# quad-hybrid-QCN-19D.net
KiCad netlist of a schematic drawn in EAGLE
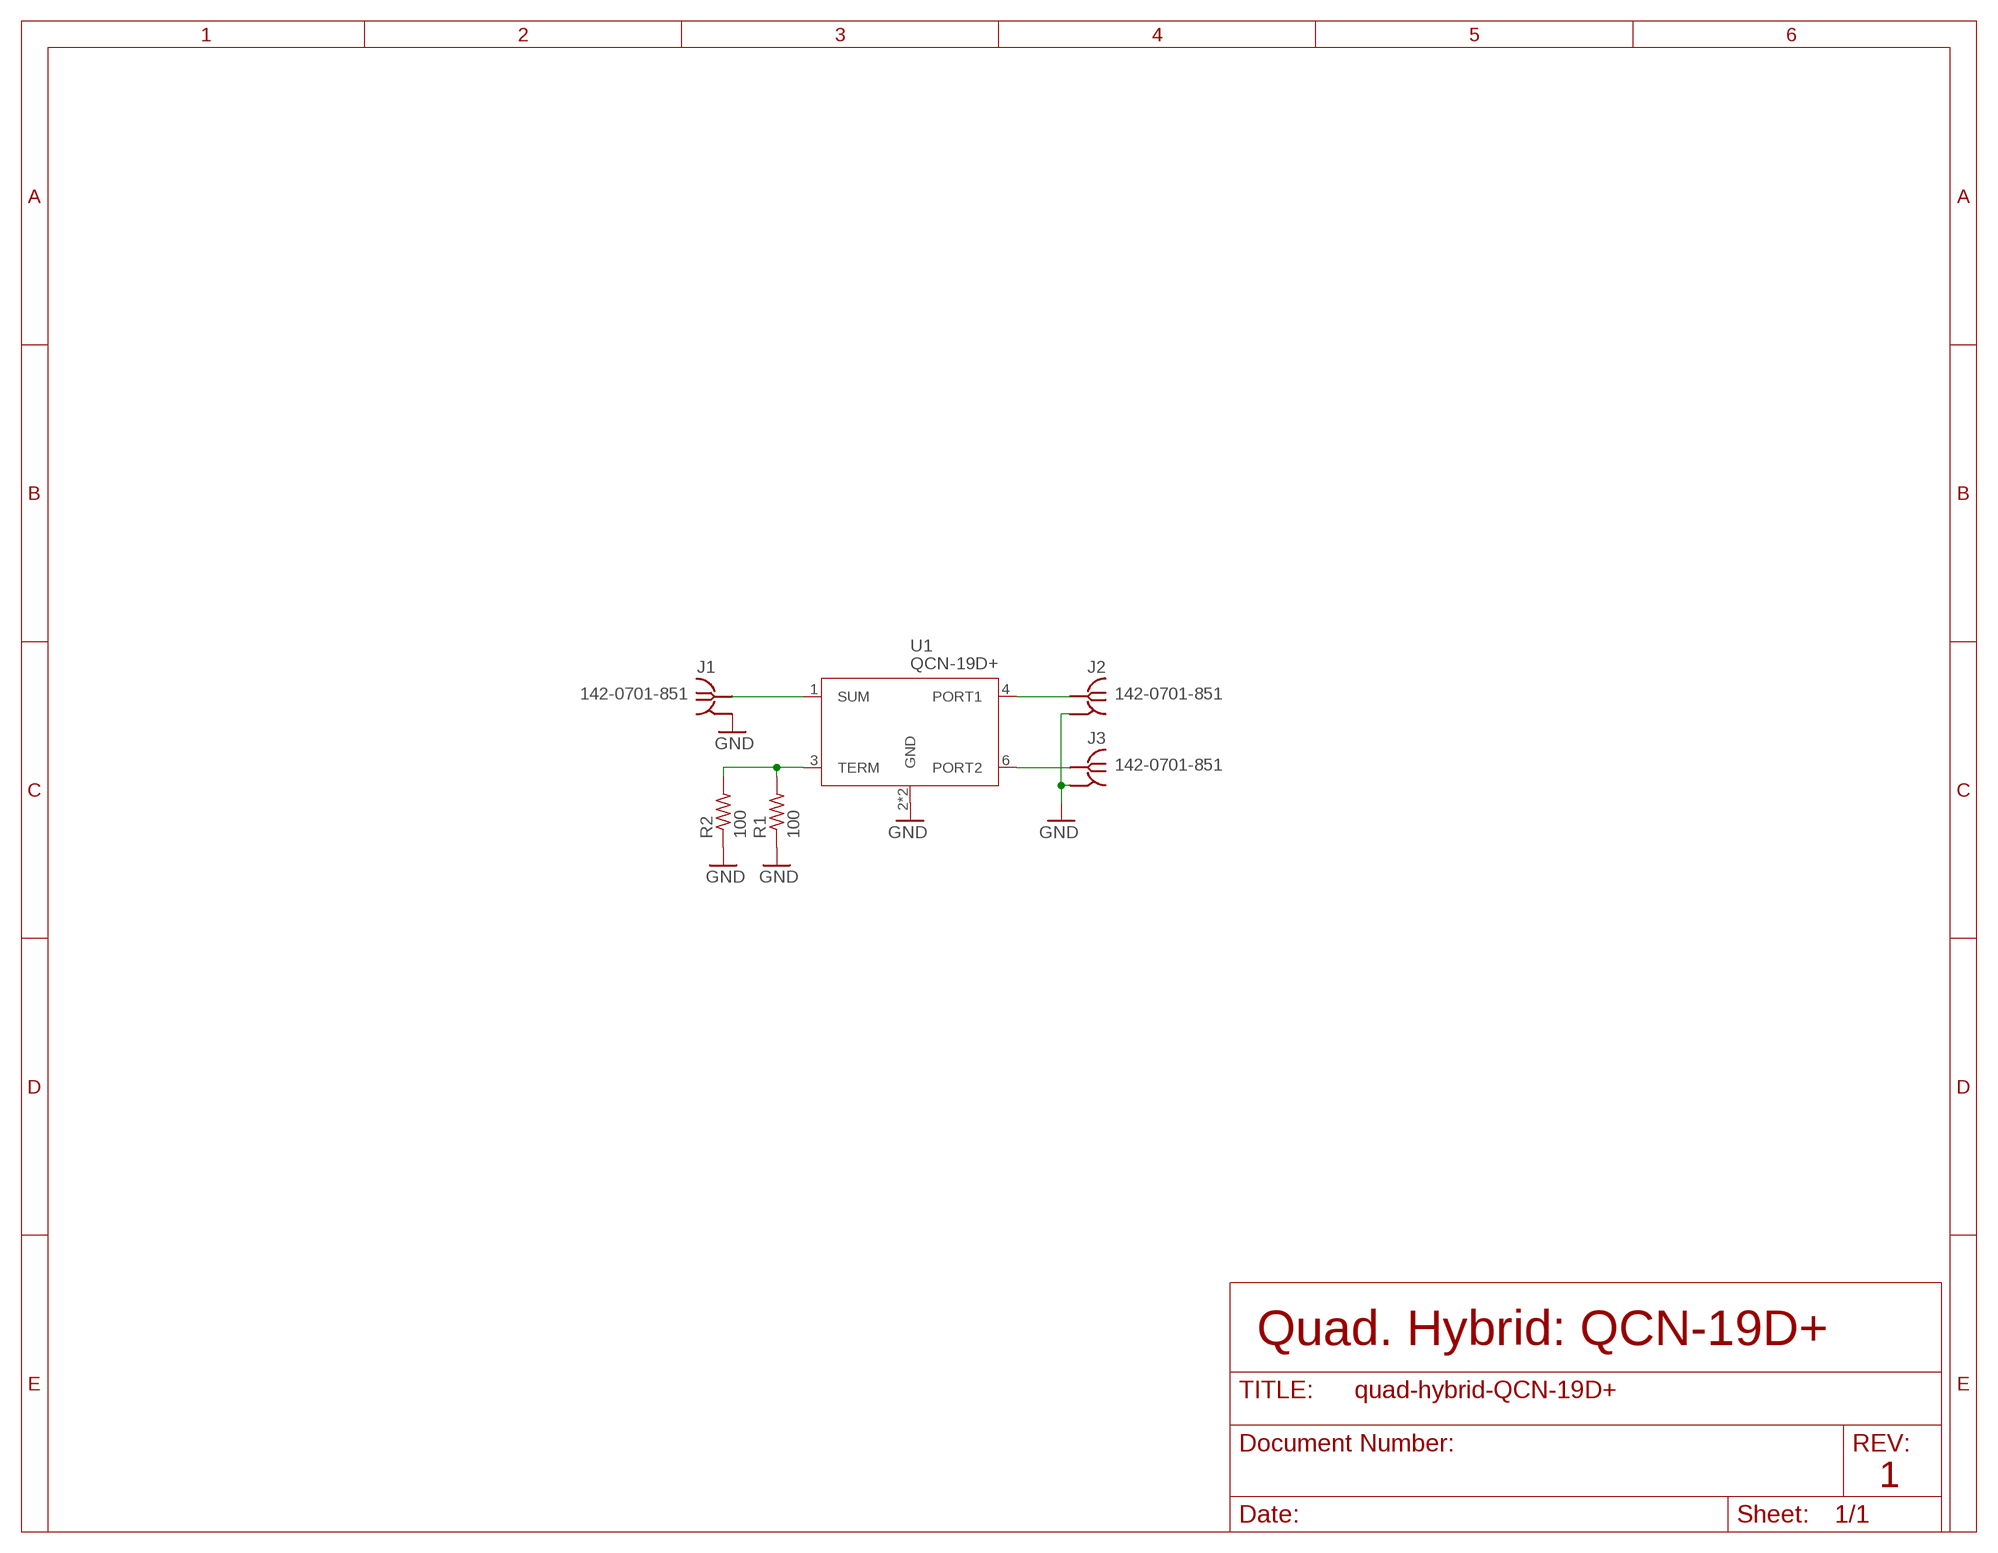
[diagram p0: schematic, sheet 1]

(export (version "E")
  (design (tool "Eeschema 10.0.6"))
  (components
    (comp (ref "J1")
      (value "142-0701-851")
      (footprint "eagle-import:142-0701-851")
      (libsource (lib "eagle-import") (part "142-0701-851"))
    )
    (comp (ref "J2")
      (value "142-0701-851")
      (footprint "eagle-import:142-0701-851")
      (libsource (lib "eagle-import") (part "142-0701-851"))
    )
    (comp (ref "J3")
      (value "142-0701-851")
      (footprint "eagle-import:142-0701-851")
      (libsource (lib "eagle-import") (part "142-0701-851"))
    )
    (comp (ref "R1")
      (value "100")
      (footprint "eagle-import:.0402-C-NOSILK")
      (libsource (lib "eagle-import") (part "R-US_0402-C-NOSILK"))
    )
    (comp (ref "R2")
      (value "100")
      (footprint "eagle-import:.0402-C-NOSILK")
      (libsource (lib "eagle-import") (part "R-US_0402-C-NOSILK"))
    )
    (comp (ref "U1")
      (value "QCN-19D+")
      (footprint "eagle-import:QCN-19D+")
      (libsource (lib "eagle-import") (part "QCN-19D+"))
    )
  )
  (nets
    (net (code "1") (name "GND") (class "Default")
      (node (ref "J1") (pin "GND1") (pinfunction "GND_GND1") (pintype "bidirectional"))
      (node (ref "J1") (pin "GND2") (pinfunction "GND_GND2") (pintype "bidirectional"))
      (node (ref "J1") (pin "GND3") (pinfunction "GND_GND3") (pintype "bidirectional"))
      (node (ref "J1") (pin "GND4") (pinfunction "GND_GND4") (pintype "bidirectional"))
      (node (ref "J2") (pin "GND1") (pinfunction "GND_GND1") (pintype "bidirectional"))
      (node (ref "J2") (pin "GND2") (pinfunction "GND_GND2") (pintype "bidirectional"))
      (node (ref "J2") (pin "GND3") (pinfunction "GND_GND3") (pintype "bidirectional"))
      (node (ref "J2") (pin "GND4") (pinfunction "GND_GND4") (pintype "bidirectional"))
      (node (ref "J3") (pin "GND1") (pinfunction "GND_GND1") (pintype "bidirectional"))
      (node (ref "J3") (pin "GND2") (pinfunction "GND_GND2") (pintype "bidirectional"))
      (node (ref "J3") (pin "GND3") (pinfunction "GND_GND3") (pintype "bidirectional"))
      (node (ref "J3") (pin "GND4") (pinfunction "GND_GND4") (pintype "bidirectional"))
      (node (ref "R1") (pin "1") (pinfunction "1_1") (pintype "passive"))
      (node (ref "R2") (pin "1") (pinfunction "1_1") (pintype "passive"))
      (node (ref "U1") (pin "2") (pinfunction "GND_2") (pintype "power_in"))
      (node (ref "U1") (pin "5") (pinfunction "GND_5") (pintype "power_in"))
    )
    (net (code "2") (name "Net-(J1-RF)") (class "Default")
      (node (ref "J1") (pin "RF1") (pinfunction "RF_RF1") (pintype "bidirectional"))
      (node (ref "U1") (pin "1") (pinfunction "SUM_1") (pintype "bidirectional"))
    )
    (net (code "3") (name "Net-(J2-RF)") (class "Default")
      (node (ref "J2") (pin "RF1") (pinfunction "RF_RF1") (pintype "bidirectional"))
      (node (ref "U1") (pin "4") (pinfunction "PORT1_4") (pintype "bidirectional"))
    )
    (net (code "4") (name "Net-(J3-RF)") (class "Default")
      (node (ref "J3") (pin "RF1") (pinfunction "RF_RF1") (pintype "bidirectional"))
      (node (ref "U1") (pin "6") (pinfunction "PORT2_6") (pintype "bidirectional"))
    )
    (net (code "5") (name "Net-(U1-TERM)") (class "Default")
      (node (ref "R1") (pin "2") (pinfunction "2_2") (pintype "passive"))
      (node (ref "R2") (pin "2") (pinfunction "2_2") (pintype "passive"))
      (node (ref "U1") (pin "3") (pinfunction "TERM_3") (pintype "bidirectional"))
    )
  )
)
